# Ram.net
KiCad netlist of a schematic drawn in Altium Designer
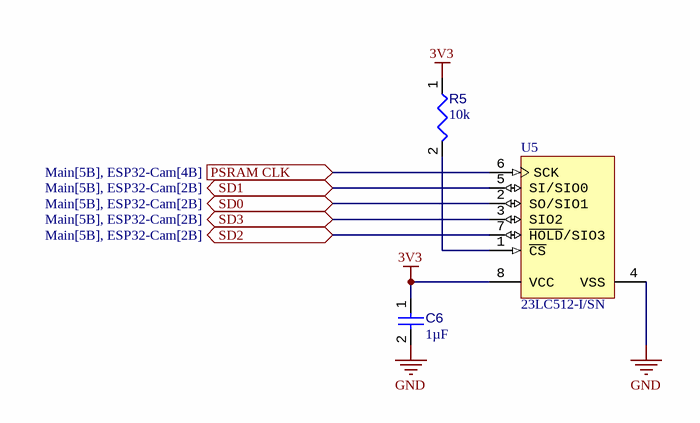
[diagram p0: Ram.SchDoc]

(export (version "E")
  (design (tool "Eeschema 10.0.6"))
  (components
    (comp (ref "C6")
      (value "1µF")
      (footprint "CAPC1608X90X40LL10T20")
      (description "Chip Capacitor, 1 uF, +/- 10%, 25 V, 0603 (1608 Metric)")
      (fields (field (name "TOLERANCE") "10%") (field (name "Comment") "Capacitor 1 uF +/- 10% 25 V 0603"))
      (libsource (lib "Bimsara Nawarathna") (part "CAP-NP-2"))
    )
    (comp (ref "R5")
      (value "10k")
      (footprint "RESC0402(1005)_L")
      (description "Chip Resistor, 10 kOhms, +/-1 %, 63 mW, -55 to 125 degC, 0402")
      (fields (field (name "POWER") "63mW") (field (name "TOLERANCE") "1%"))
      (libsource (lib "Bimsara Nawarathna") (part "RES-2"))
    )
    (comp (ref "U5")
      (value "23LC512-I/SN")
      (footprint "MCHP-SOIC-SN8_N")
      (fields (field (name "MANUFACTURER") "Microchip"))
      (libsource (lib "Altium Content Vault") (part "MCHP-23A1024_512-LC1024_512-8"))
    )
  )
  (nets
    (net (code "1") (name "/PSRAM CLK") (class "Default")
      (node (ref "U5") (pin "6") (pinfunction "SCK_6") (pintype "input"))
    )
    (net (code "2") (name "/SD0") (class "Default")
      (node (ref "U5") (pin "2") (pinfunction "SO/SIO1_2") (pintype "bidirectional"))
    )
    (net (code "3") (name "/SD1") (class "Default")
      (node (ref "U5") (pin "5") (pinfunction "SI/SIO0_5") (pintype "bidirectional"))
    )
    (net (code "4") (name "/SD2") (class "Default")
      (node (ref "U5") (pin "7") (pinfunction "~{HOLD}/SIO3_7") (pintype "bidirectional"))
    )
    (net (code "5") (name "/SD3") (class "Default")
      (node (ref "U5") (pin "3") (pinfunction "SIO2_3") (pintype "bidirectional"))
    )
    (net (code "6") (name "3V3") (class "Default")
      (node (ref "C6") (pin "1") (pinfunction "1_1") (pintype "passive"))
      (node (ref "R5") (pin "1") (pinfunction "1_1") (pintype "passive"))
      (node (ref "U5") (pin "8") (pinfunction "VCC_8") (pintype "power_in"))
    )
    (net (code "7") (name "GND") (class "Default")
      (node (ref "C6") (pin "2") (pinfunction "2_2") (pintype "passive"))
      (node (ref "U5") (pin "4") (pinfunction "VSS_4") (pintype "power_in"))
    )
    (net (code "8") (name "Net-(U5-~{CS})") (class "Default")
      (node (ref "R5") (pin "2") (pinfunction "2_2") (pintype "passive"))
      (node (ref "U5") (pin "1") (pinfunction "~{CS}_1") (pintype "input"))
    )
  )
)
